# connectors.net
KiCad netlist of a schematic drawn in Altium Designer
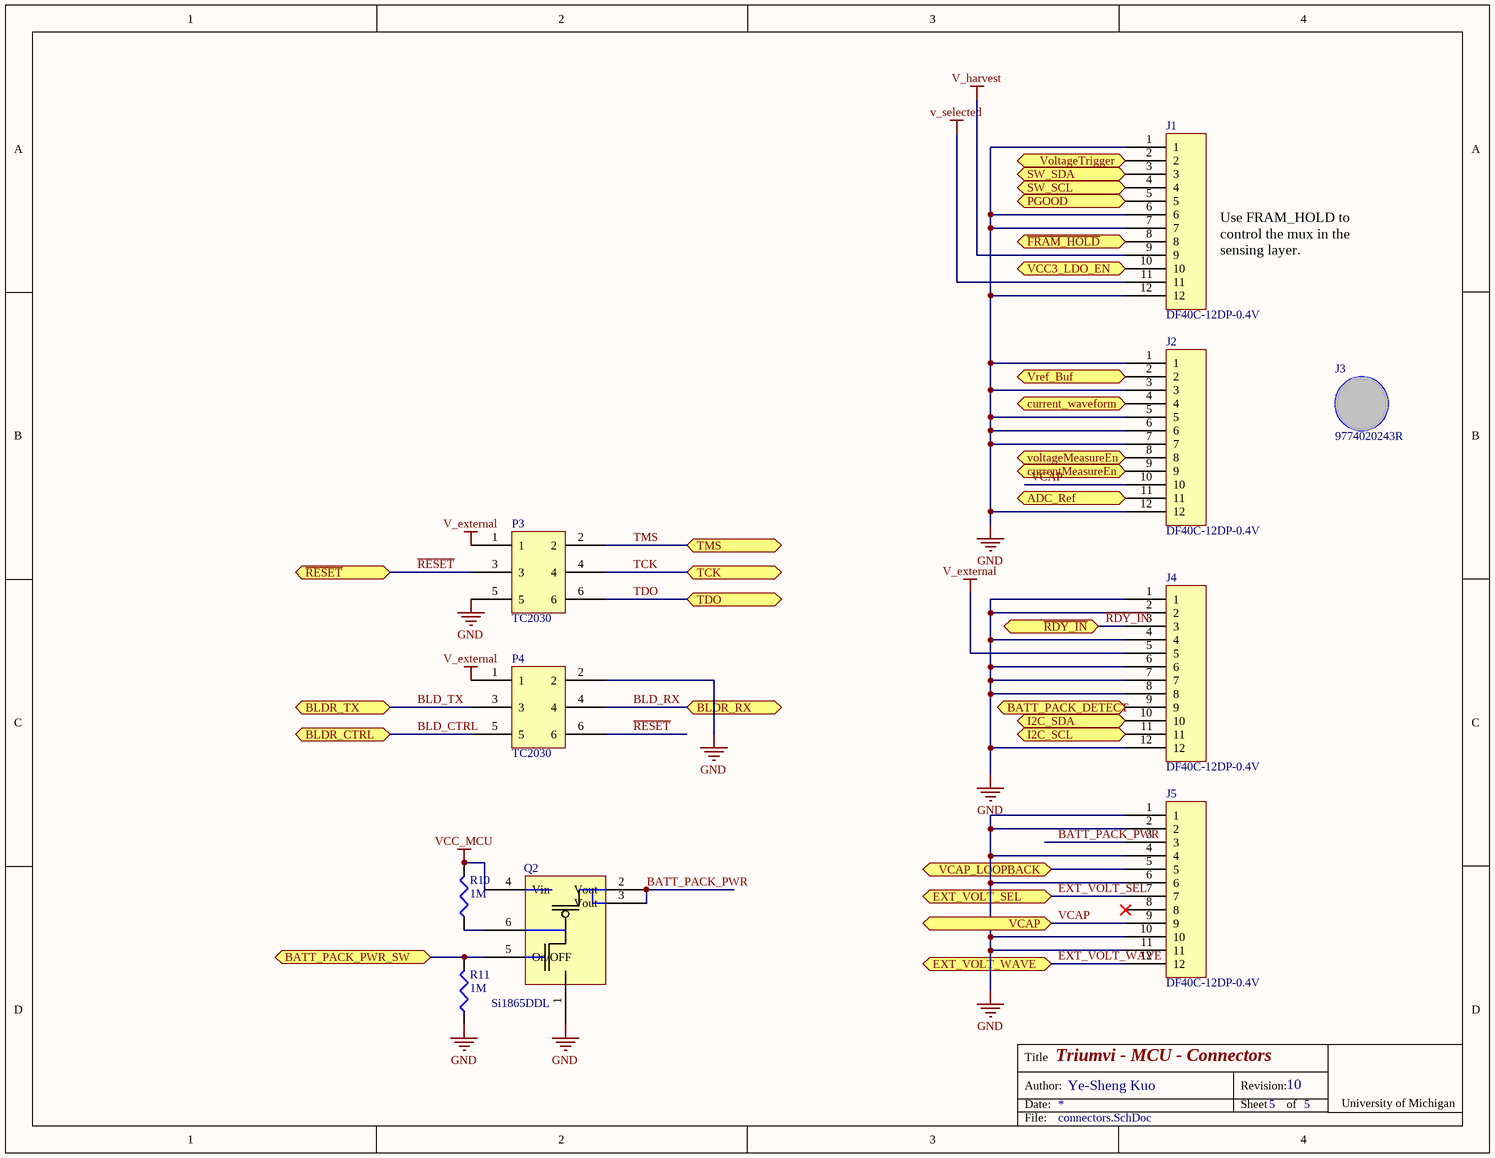
[diagram p0: connectors.SchDoc]

(export (version "E")
  (design (tool "Eeschema 10.0.6"))
  (components
    (comp (ref "J1")
      (value "DF40C-12DP-0.4V")
      (footprint "DF40C-12DP-0.4V")
      (description "Hirose BM20 Series, 0.4mm pitch, 12 pos, header")
      (libsource (lib "connectors") (part "DF40C-12DP-0.4V"))
    )
    (comp (ref "J2")
      (value "DF40C-12DP-0.4V")
      (footprint "DF40C-12DP-0.4V")
      (description "Hirose BM20 Series, 0.4mm pitch, 12 pos, header")
      (libsource (lib "connectors") (part "DF40C-12DP-0.4V"))
    )
    (comp (ref "J3")
      (value "9774020243R")
      (footprint "9774020243R")
      (description "2 mm stack height, m2 standoff")
      (libsource (lib "connectors") (part "9774020243R"))
    )
    (comp (ref "J4")
      (value "DF40C-12DP-0.4V")
      (footprint "DF40C-12DP-0.4V")
      (description "Hirose BM20 Series, 0.4mm pitch, 12 pos, header")
      (libsource (lib "connectors") (part "DF40C-12DP-0.4V"))
    )
    (comp (ref "J5")
      (value "DF40C-12DP-0.4V")
      (footprint "DF40C-12DP-0.4V")
      (description "Hirose BM20 Series, 0.4mm pitch, 12 pos, header")
      (libsource (lib "connectors") (part "DF40C-12DP-0.4V"))
    )
    (comp (ref "P3")
      (value "TC2030")
      (footprint "TC2030-IDC-NLFP")
      (description "TC2030-MCP-NL")
      (libsource (lib "connectors") (part "TC2030"))
    )
    (comp (ref "P4")
      (value "TC2030")
      (footprint "TC2030-IDC-NLFP")
      (description "TC2030-MCP-NL")
      (libsource (lib "connectors") (part "TC2030"))
    )
    (comp (ref "Q2")
      (value "Si1865DDL")
      (footprint "SC70-6")
      (description "Load Switch with Level-Shift")
      (libsource (lib "power_switch") (part "Si1865DDL"))
    )
    (comp (ref "R10")
      (value "1M")
      (footprint "0402")
      (description "Chip resistor, 1M, 0402 package")
      (fields (field (name "TOLERANCE") "1%") (field (name "POWER") "1/16 W"))
      (libsource (lib "rlc") (part "R_1M_0402"))
    )
    (comp (ref "R11")
      (value "1M")
      (footprint "0402")
      (description "Chip resistor, 1M, 0402 package")
      (fields (field (name "TOLERANCE") "1%") (field (name "POWER") "1/16 W"))
      (libsource (lib "rlc") (part "R_1M_0402"))
    )
  )
  (nets
    (net (code "1") (name "/ADC_Ref") (class "Default")
      (node (ref "J2") (pin "11") (pinfunction "11_11") (pintype "passive"))
    )
    (net (code "2") (name "/BATT_PACK_DETECT") (class "Default")
      (node (ref "J4") (pin "9") (pinfunction "9_9") (pintype "passive"))
    )
    (net (code "3") (name "/BATT_PACK_PWR") (class "Default")
      (node (ref "J5") (pin "3") (pinfunction "3_3") (pintype "passive"))
      (node (ref "Q2") (pin "2") (pinfunction "Vout_2") (pintype "passive"))
      (node (ref "Q2") (pin "3") (pinfunction "Vout_3") (pintype "passive"))
    )
    (net (code "4") (name "/BATT_PACK_PWR_SW") (class "Default")
      (node (ref "Q2") (pin "5") (pinfunction "On/OFF_5") (pintype "passive"))
      (node (ref "R11") (pin "1") (pintype "passive"))
    )
    (net (code "5") (name "/BLD_CTRL") (class "Default")
      (node (ref "P4") (pin "5") (pinfunction "5_5") (pintype "passive"))
    )
    (net (code "6") (name "/BLD_RX") (class "Default")
      (node (ref "P4") (pin "4") (pinfunction "4_4") (pintype "passive"))
    )
    (net (code "7") (name "/BLD_TX") (class "Default")
      (node (ref "P4") (pin "3") (pinfunction "3_3") (pintype "passive"))
    )
    (net (code "8") (name "/EXT_VOLT_SEL") (class "Default")
      (node (ref "J5") (pin "7") (pinfunction "7_7") (pintype "passive"))
    )
    (net (code "9") (name "/EXT_VOLT_WAVE") (class "Default")
      (node (ref "J5") (pin "12") (pinfunction "12_12") (pintype "passive"))
    )
    (net (code "10") (name "/I2C_SCL") (class "Default")
      (node (ref "J4") (pin "11") (pinfunction "11_11") (pintype "passive"))
    )
    (net (code "11") (name "/I2C_SDA") (class "Default")
      (node (ref "J4") (pin "10") (pinfunction "10_10") (pintype "passive"))
    )
    (net (code "12") (name "/PGOOD") (class "Default")
      (node (ref "J1") (pin "5") (pinfunction "5_5") (pintype "passive"))
    )
    (net (code "13") (name "/SW_SCL") (class "Default")
      (node (ref "J1") (pin "4") (pinfunction "4_4") (pintype "passive"))
    )
    (net (code "14") (name "/SW_SDA") (class "Default")
      (node (ref "J1") (pin "3") (pinfunction "3_3") (pintype "passive"))
    )
    (net (code "15") (name "/TCK") (class "Default")
      (node (ref "P3") (pin "4") (pinfunction "4_4") (pintype "passive"))
    )
    (net (code "16") (name "/TDO") (class "Default")
      (node (ref "P3") (pin "6") (pinfunction "6_6") (pintype "passive"))
    )
    (net (code "17") (name "/TMS") (class "Default")
      (node (ref "P3") (pin "2") (pinfunction "2_2") (pintype "passive"))
    )
    (net (code "18") (name "/VCAP") (class "Default")
      (node (ref "J2") (pin "10") (pinfunction "10_10") (pintype "passive"))
      (node (ref "J5") (pin "9") (pinfunction "9_9") (pintype "passive"))
    )
    (net (code "19") (name "/VCAP_LOOPBACK") (class "Default")
      (node (ref "J5") (pin "5") (pinfunction "5_5") (pintype "passive"))
    )
    (net (code "20") (name "/VCC3_LDO_EN") (class "Default")
      (node (ref "J1") (pin "10") (pinfunction "10_10") (pintype "passive"))
    )
    (net (code "21") (name "/VoltageTrigger") (class "Default")
      (node (ref "J1") (pin "2") (pinfunction "2_2") (pintype "passive"))
    )
    (net (code "22") (name "/Vref_Buf") (class "Default")
      (node (ref "J2") (pin "2") (pinfunction "2_2") (pintype "passive"))
    )
    (net (code "23") (name "/currentMeasureEn") (class "Default")
      (node (ref "J2") (pin "9") (pinfunction "9_9") (pintype "passive"))
    )
    (net (code "24") (name "/current_waveform") (class "Default")
      (node (ref "J2") (pin "4") (pinfunction "4_4") (pintype "passive"))
    )
    (net (code "25") (name "/voltageMeasureEn") (class "Default")
      (node (ref "J2") (pin "8") (pinfunction "8_8") (pintype "passive"))
    )
    (net (code "26") (name "/~{FRAM_HOLD}") (class "Default")
      (node (ref "J1") (pin "8") (pinfunction "8_8") (pintype "passive"))
    )
    (net (code "27") (name "/~{RDY_IN}") (class "Default")
      (node (ref "J4") (pin "3") (pinfunction "3_3") (pintype "passive"))
    )
    (net (code "28") (name "/~{RESET}") (class "Default")
      (node (ref "P3") (pin "3") (pinfunction "3_3") (pintype "passive"))
      (node (ref "P4") (pin "6") (pinfunction "6_6") (pintype "passive"))
    )
    (net (code "29") (name "GND") (class "Default")
      (node (ref "J1") (pin "1") (pinfunction "1_1") (pintype "passive"))
      (node (ref "J1") (pin "12") (pinfunction "12_12") (pintype "passive"))
      (node (ref "J1") (pin "6") (pinfunction "6_6") (pintype "passive"))
      (node (ref "J1") (pin "7") (pinfunction "7_7") (pintype "passive"))
      (node (ref "J2") (pin "1") (pinfunction "1_1") (pintype "passive"))
      (node (ref "J2") (pin "12") (pinfunction "12_12") (pintype "passive"))
      (node (ref "J2") (pin "3") (pinfunction "3_3") (pintype "passive"))
      (node (ref "J2") (pin "5") (pinfunction "5_5") (pintype "passive"))
      (node (ref "J2") (pin "6") (pinfunction "6_6") (pintype "passive"))
      (node (ref "J2") (pin "7") (pinfunction "7_7") (pintype "passive"))
      (node (ref "J4") (pin "1") (pinfunction "1_1") (pintype "passive"))
      (node (ref "J4") (pin "12") (pinfunction "12_12") (pintype "passive"))
      (node (ref "J4") (pin "2") (pinfunction "2_2") (pintype "passive"))
      (node (ref "J4") (pin "4") (pinfunction "4_4") (pintype "passive"))
      (node (ref "J4") (pin "6") (pinfunction "6_6") (pintype "passive"))
      (node (ref "J4") (pin "7") (pinfunction "7_7") (pintype "passive"))
      (node (ref "J4") (pin "8") (pinfunction "8_8") (pintype "passive"))
      (node (ref "J5") (pin "1") (pinfunction "1_1") (pintype "passive"))
      (node (ref "J5") (pin "10") (pinfunction "10_10") (pintype "passive"))
      (node (ref "J5") (pin "11") (pinfunction "11_11") (pintype "passive"))
      (node (ref "J5") (pin "2") (pinfunction "2_2") (pintype "passive"))
      (node (ref "J5") (pin "4") (pinfunction "4_4") (pintype "passive"))
      (node (ref "J5") (pin "6") (pinfunction "6_6") (pintype "passive"))
      (node (ref "P3") (pin "5") (pinfunction "5_5") (pintype "passive"))
      (node (ref "P4") (pin "2") (pinfunction "2_2") (pintype "passive"))
      (node (ref "Q2") (pin "1") (pinfunction "S1_1") (pintype "passive"))
      (node (ref "R11") (pin "2") (pintype "passive"))
    )
    (net (code "30") (name "Net-(Q2-D1)") (class "Default")
      (node (ref "Q2") (pin "6") (pinfunction "D1_6") (pintype "passive"))
      (node (ref "R10") (pin "2") (pintype "passive"))
    )
    (net (code "31") (name "VCC_MCU") (class "Default")
      (node (ref "Q2") (pin "4") (pinfunction "Vin_4") (pintype "passive"))
      (node (ref "R10") (pin "1") (pintype "passive"))
    )
    (net (code "32") (name "V_external") (class "Default")
      (node (ref "J4") (pin "5") (pinfunction "5_5") (pintype "passive"))
      (node (ref "P3") (pin "1") (pinfunction "1_1") (pintype "passive"))
      (node (ref "P4") (pin "1") (pinfunction "1_1") (pintype "passive"))
    )
    (net (code "33") (name "V_harvest") (class "Default")
      (node (ref "J1") (pin "9") (pinfunction "9_9") (pintype "passive"))
    )
    (net (code "34") (name "unconnected-(J5-Pad8)") (class "Default")
      (node (ref "J5") (pin "8") (pinfunction "8_8") (pintype "passive+no_connect"))
    )
    (net (code "35") (name "v_selected") (class "Default")
      (node (ref "J1") (pin "11") (pinfunction "11_11") (pintype "passive"))
    )
  )
)
